# Charge_and_System_Power-path_Management_.net
KiCad netlist of a schematic drawn in Altium Designer
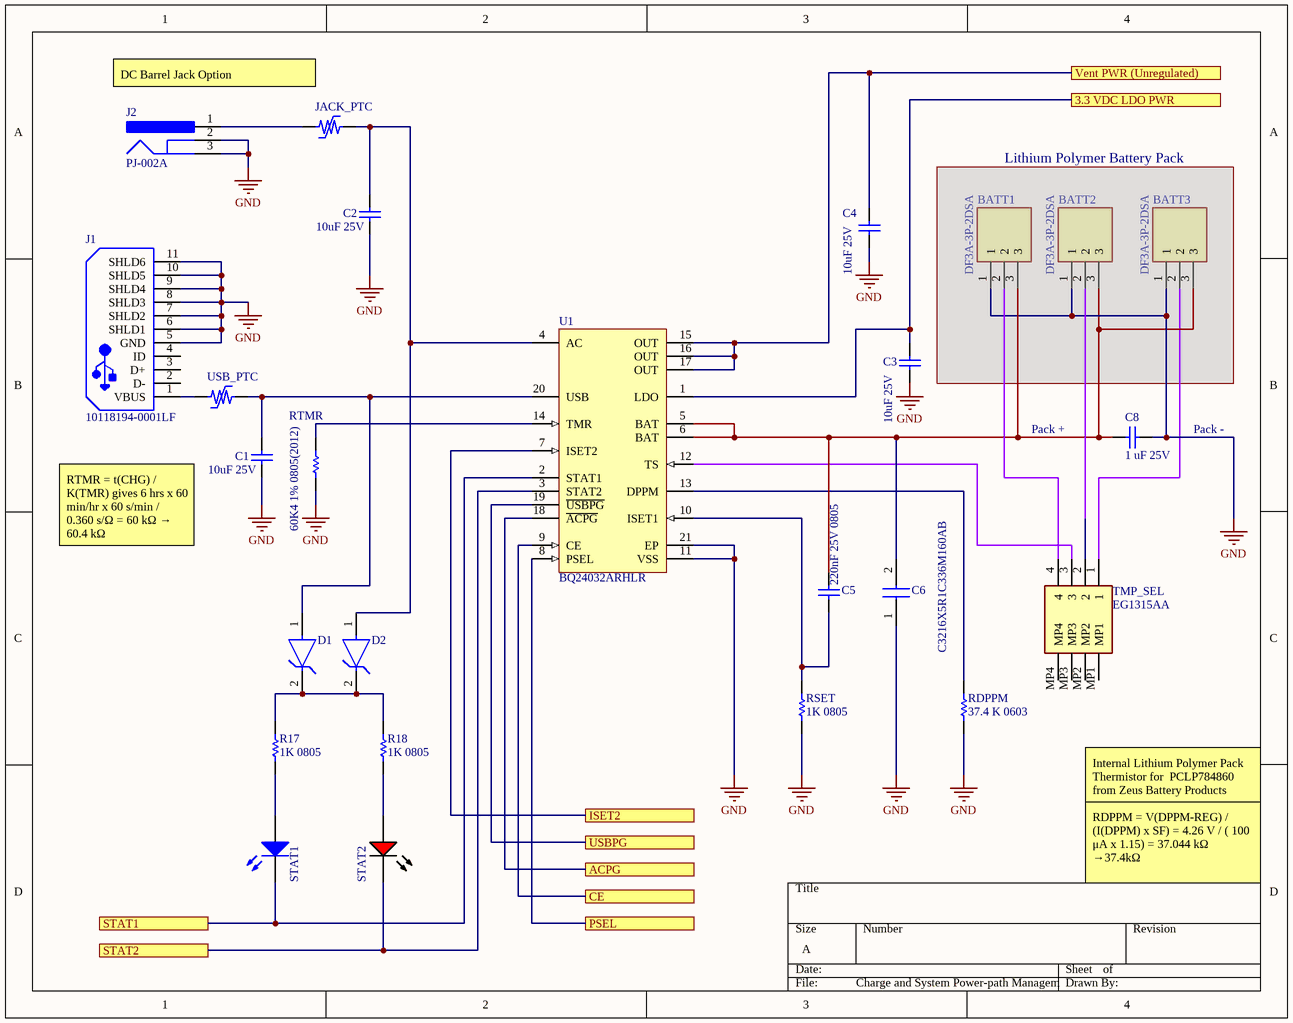
[diagram p0: Charge and System Power-path Management Circuit For Vent.SchDoc]

(export (version "E")
  (design (tool "Eeschema 10.0.6"))
  (components
    (comp (ref "BATT1")
      (value "DF3A-3P-2DSA")
      (footprint "SamacSys:SHDR3W50P0X200_1X3_800X500X500P")
      (description "Connector")
      (fields (field (name "MOUSER PART NUMBER") "798-DF3A-3P-2DSA"))
      (libsource (lib "*") (part "DF3A-3P-2DSA"))
    )
    (comp (ref "BATT2")
      (value "DF3A-3P-2DSA")
      (footprint "SamacSys:SHDR3W50P0X200_1X3_800X500X500P")
      (description "Connector")
      (fields (field (name "MOUSER PART NUMBER") "798-DF3A-3P-2DSA"))
      (libsource (lib "*") (part "DF3A-3P-2DSA"))
    )
    (comp (ref "BATT3")
      (value "DF3A-3P-2DSA")
      (footprint "SamacSys:SHDR3W50P0X200_1X3_800X500X500P")
      (description "Connector")
      (fields (field (name "MOUSER PART NUMBER") "798-DF3A-3P-2DSA"))
      (libsource (lib "*") (part "DF3A-3P-2DSA"))
    )
    (comp (ref "C1")
      (value "10uF 25V")
      (footprint "CAPC2013X135X45ML10T25")
      (fields (field (name "PART NUMBER") "GRM21BR61E106KA73L") (field (name "MANUFACTURER") "Murata"))
      (libsource (lib "Altium Content Vault") (part "CAP"))
    )
    (comp (ref "C2")
      (value "10uF 25V")
      (footprint "CAPC2013X135X45ML10T25")
      (fields (field (name "PART NUMBER") "GRM21BR61E106KA73L") (field (name "MANUFACTURER") "Murata"))
      (libsource (lib "Altium Content Vault") (part "CAP"))
    )
    (comp (ref "C3")
      (value "10uF 25V")
      (footprint "CAPC2013X135X45ML10T25")
      (fields (field (name "PART NUMBER") "GRM21BR61E106KA73L") (field (name "MANUFACTURER") "Murata"))
      (libsource (lib "Altium Content Vault") (part "CAP"))
    )
    (comp (ref "C4")
      (value "10uF 25V")
      (footprint "CAPC2013X135X45ML10T25")
      (fields (field (name "PART NUMBER") "GRM21BR61E106KA73L") (field (name "MANUFACTURER") "Murata"))
      (libsource (lib "Altium Content Vault") (part "CAP"))
    )
    (comp (ref "C5")
      (value "220nF 25V 0805")
      (footprint "CAPC0805(2012)100_M")
      (description "CAP 220nF 25V ±10% 0805 (2012 Metric) Thickness 1mm SMD")
      (fields (field (name "TOLERANCE") "Â±10%"))
      (libsource (lib "Altium Content Vault") (part "CAP"))
    )
    (comp (ref "C6")
      (value "C3216X5R1C336M160AB")
      (footprint "C1206")
      (description "Capacitor")
      (fields (field (name "MOUSER PART NUMBER") "810-C3216X5R1C336M"))
      (libsource (lib "*") (part "C3216X5R1C336M160AB"))
    )
    (comp (ref "C8")
      (value "1 uF 25V")
      (footprint "CAPC1608X90X35LL10T25")
      (description "Chip Capacitor, 1 uF, +/- 10%, 25 V, -55 to 85 degC, 0603 (1608 Metric), RoHS, Tape and Reel")
      (fields
        (field (name "TOLERANCE") "±10%")
        (field (name "PCN PART NUMBER") "X5R,X7RDielectrics23/Jan/2008")
      )
      (libsource (lib "Altium Content Vault") (part "CAP-NP-2"))
    )
    (comp (ref "D1")
      (value "MM3Z3V3B")
      (footprint "FP-MM3Z3V3B-MFG")
      (description "DIODE ZENER 3.3V 200MW SOD323F")
      (fields
        (field (name "OCTOPART") "https://octopart.com/mm3z3v3b-on+semiconductor-84329878")
        (field (name "MANUFACTURER") "ON Semiconductor")
      )
      (libsource (lib "Altium Content Vault") (part "3fba79ac723ca0a4e69928609483429"))
    )
    (comp (ref "D2")
      (value "MM3Z3V3B")
      (footprint "FP-MM3Z3V3B-MFG")
      (description "DIODE ZENER 3.3V 200MW SOD323F")
      (fields
        (field (name "OCTOPART") "https://octopart.com/mm3z3v3b-on+semiconductor-84329878")
        (field (name "MANUFACTURER") "ON Semiconductor")
      )
      (libsource (lib "Altium Content Vault") (part "3fba79ac723ca0a4e69928609483429"))
    )
    (comp (ref "J1")
      (value "10118194-0001LF")
      (footprint "FCI-10118194-0001LF-5_V")
      (description "Micro USB B Type Receptacle, 1.8 A, -55 to 85 degC, 5-Pin SMD, RoHS, Tape and Reel")
      (fields (field (name "MANUFACTURER") "Amphenol FCI"))
      (libsource (lib "Altium Content Vault") (part "USB-5-6SHLD"))
    )
    (comp (ref "J2")
      (value "PJ-002A")
      (footprint "CUI-PJ-002A_V")
      (fields (field (name "MANUFACTURER") "CUIInc."))
      (libsource (lib "Altium Content Vault") (part "JACK-2CD3-RN"))
    )
    (comp (ref "JACK_PTC")
      (value "MF-MSMF110/24X-2")
      (footprint "BOUR-MF-MSMF110-24X-2_V")
      (description "PTC Resettable Fuse, 24 V, 1.1 A, -40 to 85 degC, 2-Pin SMD, RoHS, Tape and Reel")
      (fields (field (name "MANUFACTURER") "Bourns"))
      (libsource (lib "Altium Content Vault") (part "PPTC-2"))
    )
    (comp (ref "R17")
      (value "1K 0805")
      (footprint "RESC2013X60X35ML10T20")
      (description "Chip Resistor, 1 KOhm, +/- 1%, 125 mW, -55 to 155 degC, 0805 (2012 Metric), RoHS, Tape and Reel")
      (fields (field (name "TOLERANCE") "1%") (field (name "MANUFACTURER") "Yageo"))
      (libsource (lib "Altium Content Vault") (part "RES-2"))
    )
    (comp (ref "R18")
      (value "1K 0805")
      (footprint "RESC2013X60X35ML10T20")
      (description "Chip Resistor, 1 KOhm, +/- 1%, 125 mW, -55 to 155 degC, 0805 (2012 Metric), RoHS, Tape and Reel")
      (fields (field (name "TOLERANCE") "1%") (field (name "MANUFACTURER") "Yageo"))
      (libsource (lib "Altium Content Vault") (part "RES-2"))
    )
    (comp (ref "RDPPM")
      (value "37.4 K 0603")
      (footprint "RESC1608X55X25ML10T15")
      (fields (field (name "MANUFACTURER") "Yageo") (field (name "PART NUMBER") "RC0603FR-0737K4L"))
      (libsource (lib "Altium Content Vault") (part "RES"))
    )
    (comp (ref "RSET")
      (value "1K 0805")
      (footprint "RESC2013X60X35ML10T20")
      (description "Chip Resistor, 1 KOhm, +/- 1%, 125 mW, -55 to 155 degC, 0805 (2012 Metric), RoHS, Tape and Reel")
      (fields (field (name "TOLERANCE") "1%") (field (name "MANUFACTURER") "Yageo"))
      (libsource (lib "Altium Content Vault") (part "RES-2"))
    )
    (comp (ref "RTMR")
      (value "60K4 1% 0805(2012)")
      (footprint "RESC0805(2012)_M")
      (description "60K4 0.125W 1% 0805 (2012 Metric)  SMD")
      (fields (field (name "POWER") "0.125 W") (field (name "TOLERANCE") "1 %"))
      (libsource (lib "Altium Content Vault") (part "RES"))
    )
    (comp (ref "STAT1")
      (value "~")
      (footprint "1206_A")
      (description "LTST-C150GKT\r\n1206 green led")
      (fields (field (name "PARTNUMBER") "LTST-C150GKT"))
      (libsource (lib "Altium Content Vault") (part "WE-LED_K1A2-2"))
    )
    (comp (ref "STAT2")
      (value "LTST-C150KRKT")
      (footprint "LTST-C150KRKT_V")
      (description "LED Red, 62.5 mW, 50 mA, -30 to 85 degC, 2-Pin SMD, RoHS, Tape and Reel")
      (fields (field (name "MANUFACTURER") "Lite-On"))
      (libsource (lib "Altium Content Vault") (part "LED-RED-AK-2"))
    )
    (comp (ref "TMP_SEL")
      (value "EG1315AA")
      (footprint "SamacSys:EG1315AA")
      (description "Switch")
      (fields (field (name "MOUSER PART NUMBER") "612-EG1315AA"))
      (libsource (lib "*") (part "EG1315AA"))
    )
    (comp (ref "U1")
      (value "BQ24032ARHLR")
      (footprint "RHL0020A_V")
      (fields (field (name "MANUFACTURER") "Texas Instruments"))
      (libsource (lib "Altium Content Vault") (part "TI-BQ24032ARHL20-3050X2050TP"))
    )
    (comp (ref "USB_PTC")
      (value "MF-MSMF110/24X-2")
      (footprint "BOUR-MF-MSMF110-24X-2_V")
      (description "PTC Resettable Fuse, 24 V, 1.1 A, -40 to 85 degC, 2-Pin SMD, RoHS, Tape and Reel")
      (fields (field (name "MANUFACTURER") "Bourns"))
      (libsource (lib "Altium Content Vault") (part "PPTC-2"))
    )
  )
  (nets
    (net (code "1") (name "/3.3 VDC LDO PWR") (class "Default")
      (node (ref "C3") (pin "2") (pinfunction "2_2") (pintype "passive"))
      (node (ref "U1") (pin "1") (pinfunction "LDO_1") (pintype "power_in"))
    )
    (net (code "2") (name "/ACPG") (class "Default")
      (node (ref "U1") (pin "18") (pinfunction "~{ACPG}_18") (pintype "open_collector"))
    )
    (net (code "3") (name "/CE") (class "Default")
      (node (ref "U1") (pin "9") (pinfunction "CE_9") (pintype "input"))
    )
    (net (code "4") (name "/ISET2") (class "Default")
      (node (ref "U1") (pin "7") (pinfunction "ISET2_7") (pintype "input"))
    )
    (net (code "5") (name "/PSEL") (class "Default")
      (node (ref "U1") (pin "8") (pinfunction "PSEL_8") (pintype "input"))
    )
    (net (code "6") (name "/STAT1") (class "Default")
      (node (ref "STAT1") (pin "1") (pinfunction "K_1") (pintype "passive"))
      (node (ref "U1") (pin "2") (pinfunction "STAT1_2") (pintype "open_collector"))
    )
    (net (code "7") (name "/STAT2") (class "Default")
      (node (ref "STAT2") (pin "2") (pinfunction "K_2") (pintype "passive"))
      (node (ref "U1") (pin "3") (pinfunction "STAT2_3") (pintype "open_collector"))
    )
    (net (code "8") (name "/USBPG") (class "Default")
      (node (ref "U1") (pin "19") (pinfunction "~{USBPG}_19") (pintype "open_collector"))
    )
    (net (code "9") (name "/Vent PWR (Unregulated)") (class "Default")
      (node (ref "C4") (pin "2") (pinfunction "2_2") (pintype "passive"))
      (node (ref "U1") (pin "15") (pinfunction "OUT_15") (pintype "power_in"))
      (node (ref "U1") (pin "16") (pinfunction "OUT_16") (pintype "power_in"))
      (node (ref "U1") (pin "17") (pinfunction "OUT_17") (pintype "power_in"))
    )
    (net (code "10") (name "GND") (class "Default")
      (node (ref "BATT1") (pin "1") (pinfunction "1_1") (pintype "passive"))
      (node (ref "BATT2") (pin "1") (pinfunction "1_1") (pintype "passive"))
      (node (ref "BATT3") (pin "1") (pinfunction "1_1") (pintype "passive"))
      (node (ref "C1") (pin "1") (pinfunction "1_1") (pintype "passive"))
      (node (ref "C2") (pin "1") (pinfunction "1_1") (pintype "passive"))
      (node (ref "C3") (pin "1") (pinfunction "1_1") (pintype "passive"))
      (node (ref "C4") (pin "1") (pinfunction "1_1") (pintype "passive"))
      (node (ref "C6") (pin "1") (pinfunction "1_1") (pintype "passive"))
      (node (ref "C8") (pin "1") (pinfunction "1_1") (pintype "passive"))
      (node (ref "J1") (pin "10") (pinfunction "SHLD5_10") (pintype "passive"))
      (node (ref "J1") (pin "11") (pinfunction "SHLD6_11") (pintype "passive"))
      (node (ref "J1") (pin "5") (pinfunction "GND_5") (pintype "passive"))
      (node (ref "J1") (pin "6") (pinfunction "SHLD1_6") (pintype "passive"))
      (node (ref "J1") (pin "7") (pinfunction "SHLD2_7") (pintype "passive"))
      (node (ref "J1") (pin "8") (pinfunction "SHLD3_8") (pintype "passive"))
      (node (ref "J1") (pin "9") (pinfunction "SHLD4_9") (pintype "passive"))
      (node (ref "J2") (pin "2") (pinfunction "2_2") (pintype "passive"))
      (node (ref "J2") (pin "3") (pinfunction "3_3") (pintype "passive"))
      (node (ref "RDPPM") (pin "1") (pinfunction "1_1") (pintype "passive"))
      (node (ref "RSET") (pin "1") (pinfunction "1_1") (pintype "passive"))
      (node (ref "RTMR") (pin "1") (pinfunction "1_1") (pintype "passive"))
      (node (ref "U1") (pin "11") (pinfunction "VSS_11") (pintype "power_in"))
      (node (ref "U1") (pin "21") (pinfunction "EP_21") (pintype "passive"))
    )
    (net (code "11") (name "Net-(BATT1-Pad2)") (class "Default")
      (node (ref "BATT1") (pin "2") (pinfunction "2_2") (pintype "passive"))
      (node (ref "TMP_SEL") (pin "4") (pinfunction "4_4") (pintype "passive"))
    )
    (net (code "12") (name "Net-(BATT1-Pad3)") (class "Default")
      (node (ref "BATT1") (pin "3") (pinfunction "3_3") (pintype "passive"))
      (node (ref "BATT2") (pin "3") (pinfunction "3_3") (pintype "passive"))
      (node (ref "BATT3") (pin "3") (pinfunction "3_3") (pintype "passive"))
      (node (ref "C5") (pin "2") (pinfunction "2_2") (pintype "passive"))
      (node (ref "C6") (pin "2") (pinfunction "2_2") (pintype "passive"))
      (node (ref "C8") (pin "2") (pinfunction "2_2") (pintype "passive"))
      (node (ref "U1") (pin "5") (pinfunction "BAT_5") (pintype "power_in"))
      (node (ref "U1") (pin "6") (pinfunction "BAT_6") (pintype "power_in"))
    )
    (net (code "13") (name "Net-(BATT2-Pad2)") (class "Default")
      (node (ref "BATT2") (pin "2") (pinfunction "2_2") (pintype "passive"))
      (node (ref "TMP_SEL") (pin "2") (pinfunction "2_2") (pintype "passive"))
    )
    (net (code "14") (name "Net-(BATT3-Pad2)") (class "Default")
      (node (ref "BATT3") (pin "2") (pinfunction "2_2") (pintype "passive"))
      (node (ref "TMP_SEL") (pin "1") (pinfunction "1_1") (pintype "passive"))
    )
    (net (code "15") (name "Net-(D1-A)") (class "Default")
      (node (ref "C1") (pin "2") (pinfunction "2_2") (pintype "passive"))
      (node (ref "D1") (pin "1") (pinfunction "A_1") (pintype "passive"))
      (node (ref "U1") (pin "20") (pinfunction "USB_20") (pintype "power_in"))
      (node (ref "USB_PTC") (pin "2") (pinfunction "2_2") (pintype "passive"))
    )
    (net (code "16") (name "Net-(D1-C)") (class "Default")
      (node (ref "D1") (pin "2") (pinfunction "C_2") (pintype "passive"))
      (node (ref "D2") (pin "2") (pinfunction "C_2") (pintype "passive"))
      (node (ref "R17") (pin "2") (pinfunction "2_2") (pintype "passive"))
      (node (ref "R18") (pin "2") (pinfunction "2_2") (pintype "passive"))
    )
    (net (code "17") (name "Net-(D2-A)") (class "Default")
      (node (ref "C2") (pin "2") (pinfunction "2_2") (pintype "passive"))
      (node (ref "D2") (pin "1") (pinfunction "A_1") (pintype "passive"))
      (node (ref "JACK_PTC") (pin "2") (pinfunction "2_2") (pintype "passive"))
      (node (ref "U1") (pin "4") (pinfunction "AC_4") (pintype "power_in"))
    )
    (net (code "18") (name "Net-(J1-VBUS)") (class "Default")
      (node (ref "J1") (pin "1") (pinfunction "VBUS_1") (pintype "passive"))
      (node (ref "USB_PTC") (pin "1") (pinfunction "1_1") (pintype "passive"))
    )
    (net (code "19") (name "Net-(J2-Pad1)") (class "Default")
      (node (ref "J2") (pin "1") (pinfunction "1_1") (pintype "passive"))
      (node (ref "JACK_PTC") (pin "1") (pinfunction "1_1") (pintype "passive"))
    )
    (net (code "20") (name "Net-(STAT1-A)") (class "Default")
      (node (ref "R17") (pin "1") (pinfunction "1_1") (pintype "passive"))
      (node (ref "STAT1") (pin "2") (pinfunction "A_2") (pintype "passive"))
    )
    (net (code "21") (name "Net-(STAT2-A)") (class "Default")
      (node (ref "R18") (pin "1") (pinfunction "1_1") (pintype "passive"))
      (node (ref "STAT2") (pin "1") (pinfunction "A_1") (pintype "passive"))
    )
    (net (code "22") (name "Net-(U1-DPPM)") (class "Default")
      (node (ref "RDPPM") (pin "2") (pinfunction "2_2") (pintype "passive"))
      (node (ref "U1") (pin "13") (pinfunction "DPPM_13") (pintype "passive"))
    )
    (net (code "23") (name "Net-(U1-ISET1)") (class "Default")
      (node (ref "C5") (pin "1") (pinfunction "1_1") (pintype "passive"))
      (node (ref "RSET") (pin "2") (pinfunction "2_2") (pintype "passive"))
      (node (ref "U1") (pin "10") (pinfunction "ISET1_10") (pintype "input"))
    )
    (net (code "24") (name "Net-(U1-TMR)") (class "Default")
      (node (ref "RTMR") (pin "2") (pinfunction "2_2") (pintype "passive"))
      (node (ref "U1") (pin "14") (pinfunction "TMR_14") (pintype "input"))
    )
    (net (code "25") (name "Net-(U1-TS)") (class "Default")
      (node (ref "TMP_SEL") (pin "3") (pinfunction "3_3") (pintype "passive"))
      (node (ref "U1") (pin "12") (pinfunction "TS_12") (pintype "input"))
    )
    (net (code "26") (name "unconnected-(J1-D+-Pad3)") (class "Default")
      (node (ref "J1") (pin "3") (pinfunction "D+_3") (pintype "passive"))
    )
    (net (code "27") (name "unconnected-(J1-D--Pad2)") (class "Default")
      (node (ref "J1") (pin "2") (pinfunction "D-_2") (pintype "passive"))
    )
    (net (code "28") (name "unconnected-(J1-ID-Pad4)") (class "Default")
      (node (ref "J1") (pin "4") (pinfunction "ID_4") (pintype "passive"))
    )
    (net (code "29") (name "unconnected-(TMP_SEL-PadMP1)") (class "Default")
      (node (ref "TMP_SEL") (pin "MP1") (pinfunction "MP1_MP1") (pintype "passive"))
    )
    (net (code "30") (name "unconnected-(TMP_SEL-PadMP2)") (class "Default")
      (node (ref "TMP_SEL") (pin "MP2") (pinfunction "MP2_MP2") (pintype "passive"))
    )
    (net (code "31") (name "unconnected-(TMP_SEL-PadMP3)") (class "Default")
      (node (ref "TMP_SEL") (pin "MP3") (pinfunction "MP3_MP3") (pintype "passive"))
    )
    (net (code "32") (name "unconnected-(TMP_SEL-PadMP4)") (class "Default")
      (node (ref "TMP_SEL") (pin "MP4") (pinfunction "MP4_MP4") (pintype "passive"))
    )
  )
)
